# LPFlasher-v2_0.net
KiCad netlist of a schematic drawn in EAGLE
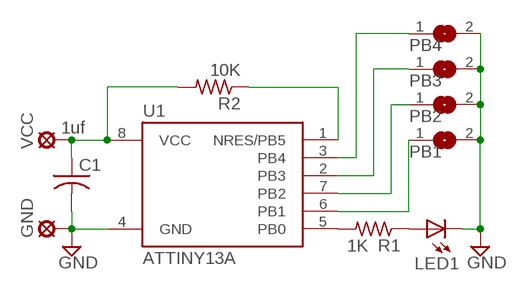
[diagram p0: schematic, sheet 1]

(export (version "E")
  (design (tool "Eeschema 10.0.6"))
  (components
    (comp (ref "C1")
      (value "1uf")
      (footprint "eagle-import:C025-024X044")
      (libsource (lib "eagle-import") (part "C-US025-024X044"))
    )
    (comp (ref "GND")
      (value "LSP13")
      (footprint "eagle-import:LSP13")
      (libsource (lib "eagle-import") (part "LSP13"))
    )
    (comp (ref "LED1")
      (value "LED5MM")
      (footprint "eagle-import:LED5MM")
      (libsource (lib "eagle-import") (part "LED5MM"))
    )
    (comp (ref "PB1")
      (value "JUMPER")
      (footprint "eagle-import:SJW")
      (libsource (lib "eagle-import") (part "JUMPER"))
    )
    (comp (ref "PB2")
      (value "JUMPER")
      (footprint "eagle-import:SJW")
      (libsource (lib "eagle-import") (part "JUMPER"))
    )
    (comp (ref "PB3")
      (value "JUMPER")
      (footprint "eagle-import:SJW")
      (libsource (lib "eagle-import") (part "JUMPER"))
    )
    (comp (ref "PB4")
      (value "JUMPER")
      (footprint "eagle-import:SJW")
      (libsource (lib "eagle-import") (part "JUMPER"))
    )
    (comp (ref "R1")
      (value "1K")
      (footprint "eagle-import:0204V")
      (libsource (lib "eagle-import") (part "R-US_0204/2V"))
    )
    (comp (ref "R2")
      (value "10K")
      (footprint "eagle-import:0204V")
      (libsource (lib "eagle-import") (part "R-US_0204/2V"))
    )
    (comp (ref "U1")
      (value "ATTINY13A")
      (footprint "eagle-import:PDIP08_300MIL")
      (libsource (lib "eagle-import") (part "ATTINY25P-"))
    )
    (comp (ref "VCC")
      (value "LSP13")
      (footprint "eagle-import:LSP13")
      (libsource (lib "eagle-import") (part "LSP13"))
    )
  )
  (nets
    (net (code "1") (name "GND") (class "Default")
      (node (ref "C1") (pin "2") (pinfunction "2_2") (pintype "passive"))
      (node (ref "GND") (pin "MP") (pinfunction "MP_MP") (pintype "passive"))
      (node (ref "LED1") (pin "K") (pinfunction "C_K") (pintype "passive"))
      (node (ref "PB1") (pin "2") (pinfunction "2_2") (pintype "passive"))
      (node (ref "PB2") (pin "2") (pinfunction "2_2") (pintype "passive"))
      (node (ref "PB3") (pin "2") (pinfunction "2_2") (pintype "passive"))
      (node (ref "PB4") (pin "2") (pinfunction "2_2") (pintype "passive"))
      (node (ref "U1") (pin "4") (pinfunction "GND_4") (pintype "power_in"))
    )
    (net (code "2") (name "Net-(LED1-PadA)") (class "Default")
      (node (ref "LED1") (pin "A") (pinfunction "A_A") (pintype "passive"))
      (node (ref "R1") (pin "1") (pinfunction "1_1") (pintype "passive"))
    )
    (net (code "3") (name "Net-(U1-NRES{slash}PB5)") (class "Default")
      (node (ref "R2") (pin "1") (pinfunction "1_1") (pintype "passive"))
      (node (ref "U1") (pin "1") (pinfunction "NRES/PB5_1") (pintype "bidirectional"))
    )
    (net (code "4") (name "Net-(U1-PB0)") (class "Default")
      (node (ref "R1") (pin "2") (pinfunction "2_2") (pintype "passive"))
      (node (ref "U1") (pin "5") (pinfunction "PB0_5") (pintype "bidirectional"))
    )
    (net (code "5") (name "Net-(U1-PB1)") (class "Default")
      (node (ref "PB1") (pin "1") (pinfunction "1_1") (pintype "passive"))
      (node (ref "U1") (pin "6") (pinfunction "PB1_6") (pintype "bidirectional"))
    )
    (net (code "6") (name "Net-(U1-PB2)") (class "Default")
      (node (ref "PB2") (pin "1") (pinfunction "1_1") (pintype "passive"))
      (node (ref "U1") (pin "7") (pinfunction "PB2_7") (pintype "bidirectional"))
    )
    (net (code "7") (name "Net-(U1-PB3)") (class "Default")
      (node (ref "PB3") (pin "1") (pinfunction "1_1") (pintype "passive"))
      (node (ref "U1") (pin "2") (pinfunction "PB3_2") (pintype "bidirectional"))
    )
    (net (code "8") (name "Net-(U1-PB4)") (class "Default")
      (node (ref "PB4") (pin "1") (pinfunction "1_1") (pintype "passive"))
      (node (ref "U1") (pin "3") (pinfunction "PB4_3") (pintype "bidirectional"))
    )
    (net (code "9") (name "Net-(U1-VCC)") (class "Default")
      (node (ref "C1") (pin "1") (pinfunction "1_1") (pintype "passive"))
      (node (ref "R2") (pin "2") (pinfunction "2_2") (pintype "passive"))
      (node (ref "U1") (pin "8") (pinfunction "VCC_8") (pintype "power_in"))
      (node (ref "VCC") (pin "MP") (pinfunction "MP_MP") (pintype "passive"))
    )
  )
)
